# Neural_Interface.net
KiCad netlist of a schematic drawn in Altium Designer
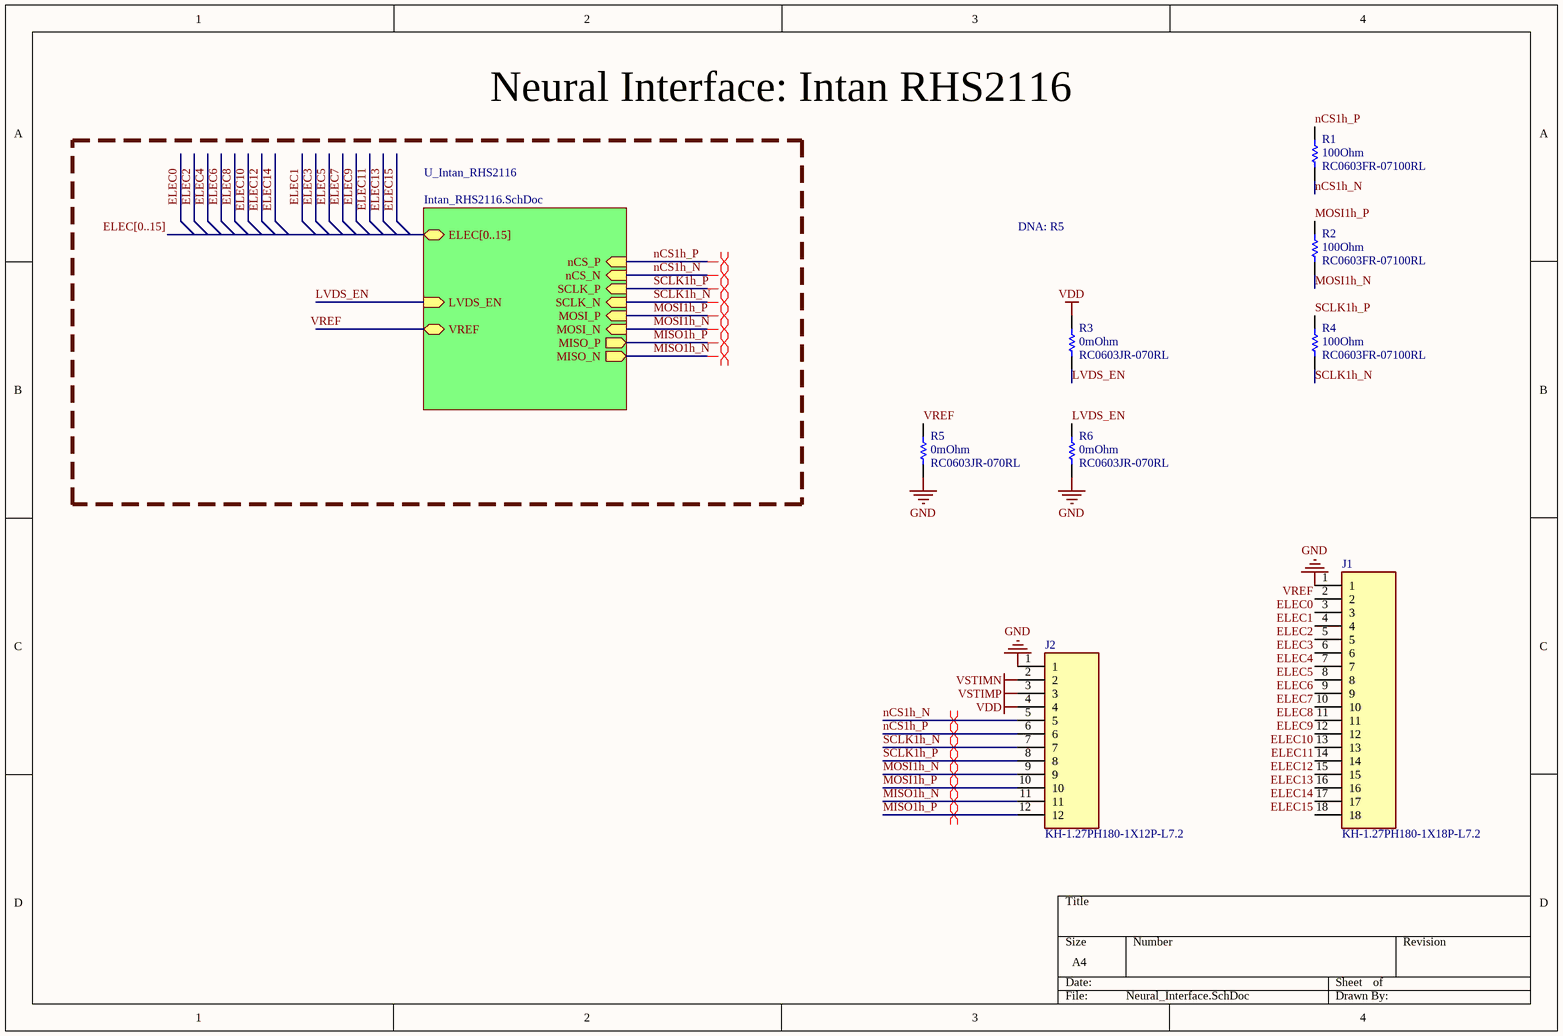
[diagram p0: Neural_Interface.SchDoc]

(export (version "E")
  (design (tool "Eeschema 10.0.6"))
  (components
    (comp (ref "J1")
      (value "KH-1.27PH180-1X18P-L7.2")
      (footprint "KH-1.27PH180-1X18P-L7.2")
      (libsource (lib "Neural_Interface") (part "KH-1.27PH180-1X18P-L7.2"))
    )
    (comp (ref "J2")
      (value "KH-1.27PH180-1X12P-L7.2")
      (footprint "KH-1.27PH180-1X12P-L7.2")
      (libsource (lib "Neural_Interface") (part "KH-1.27PH180-1X12P-L7.2"))
    )
    (comp (ref "R1")
      (value "RC0603FR-07100RL")
      (footprint "RESC1608X55X25ML10T15")
      (description "Chip Resistor, 100 Ohm, +/- 1%, 0.1 W, -55 to 155 degC, 0603 (1608 Metric), RoHS, Tape and Reel")
      (fields
        (field (name "TOLERANCE") "1%")
        (field (name "RESISTANCE") "100Ohm")
        (field (name "MANUFACTURER") "Yageo")
      )
      (libsource (lib "Altium Content Vault") (part "RES-2"))
    )
    (comp (ref "R2")
      (value "RC0603FR-07100RL")
      (footprint "RESC1608X55X25ML10T15")
      (description "Chip Resistor, 100 Ohm, +/- 1%, 0.1 W, -55 to 155 degC, 0603 (1608 Metric), RoHS, Tape and Reel")
      (fields
        (field (name "TOLERANCE") "1%")
        (field (name "RESISTANCE") "100Ohm")
        (field (name "MANUFACTURER") "Yageo")
      )
      (libsource (lib "Altium Content Vault") (part "RES-2"))
    )
    (comp (ref "R3")
      (value "RC0603JR-070RL")
      (footprint "RESC1608X55X25ML10T15")
      (description "Chip Resistor, 0 Ohm, +/- 5%, 0.1 W, -55 to 155 degC, 0603 (1608 Metric), RoHS, Tape and Reel")
      (fields
        (field (name "TOLERANCE") "5%")
        (field (name "RESISTANCE") "0mOhm")
        (field (name "MANUFACTURER") "Yageo")
      )
      (libsource (lib "Altium Content Vault") (part "RES-2"))
    )
    (comp (ref "R4")
      (value "RC0603FR-07100RL")
      (footprint "RESC1608X55X25ML10T15")
      (description "Chip Resistor, 100 Ohm, +/- 1%, 0.1 W, -55 to 155 degC, 0603 (1608 Metric), RoHS, Tape and Reel")
      (fields
        (field (name "TOLERANCE") "1%")
        (field (name "RESISTANCE") "100Ohm")
        (field (name "MANUFACTURER") "Yageo")
      )
      (libsource (lib "Altium Content Vault") (part "RES-2"))
    )
    (comp (ref "R5")
      (value "RC0603JR-070RL")
      (footprint "RESC1608X55X25ML10T15")
      (description "Chip Resistor, 0 Ohm, +/- 5%, 0.1 W, -55 to 155 degC, 0603 (1608 Metric), RoHS, Tape and Reel")
      (fields
        (field (name "TOLERANCE") "5%")
        (field (name "RESISTANCE") "0mOhm")
        (field (name "MANUFACTURER") "Yageo")
      )
      (libsource (lib "Altium Content Vault") (part "RES-2"))
    )
    (comp (ref "R6")
      (value "RC0603JR-070RL")
      (footprint "RESC1608X55X25ML10T15")
      (description "Chip Resistor, 0 Ohm, +/- 5%, 0.1 W, -55 to 155 degC, 0603 (1608 Metric), RoHS, Tape and Reel")
      (fields
        (field (name "TOLERANCE") "5%")
        (field (name "RESISTANCE") "0mOhm")
        (field (name "MANUFACTURER") "Yageo")
      )
      (libsource (lib "Altium Content Vault") (part "RES-2"))
    )
  )
  (nets
    (net (code "1") (name "/ELEC0") (class "Default")
      (node (ref "J1") (pin "3") (pinfunction "3_3") (pintype "passive"))
    )
    (net (code "2") (name "/ELEC1") (class "Default")
      (node (ref "J1") (pin "4") (pinfunction "4_4") (pintype "passive"))
    )
    (net (code "3") (name "/ELEC2") (class "Default")
      (node (ref "J1") (pin "5") (pinfunction "5_5") (pintype "passive"))
    )
    (net (code "4") (name "/ELEC3") (class "Default")
      (node (ref "J1") (pin "6") (pinfunction "6_6") (pintype "passive"))
    )
    (net (code "5") (name "/ELEC4") (class "Default")
      (node (ref "J1") (pin "7") (pinfunction "7_7") (pintype "passive"))
    )
    (net (code "6") (name "/ELEC5") (class "Default")
      (node (ref "J1") (pin "8") (pinfunction "8_8") (pintype "passive"))
    )
    (net (code "7") (name "/ELEC6") (class "Default")
      (node (ref "J1") (pin "9") (pinfunction "9_9") (pintype "passive"))
    )
    (net (code "8") (name "/ELEC7") (class "Default")
      (node (ref "J1") (pin "10") (pinfunction "10_10") (pintype "passive"))
    )
    (net (code "9") (name "/ELEC8") (class "Default")
      (node (ref "J1") (pin "11") (pinfunction "11_11") (pintype "passive"))
    )
    (net (code "10") (name "/ELEC9") (class "Default")
      (node (ref "J1") (pin "12") (pinfunction "12_12") (pintype "passive"))
    )
    (net (code "11") (name "/ELEC10") (class "Default")
      (node (ref "J1") (pin "13") (pinfunction "13_13") (pintype "passive"))
    )
    (net (code "12") (name "/ELEC11") (class "Default")
      (node (ref "J1") (pin "14") (pinfunction "14_14") (pintype "passive"))
    )
    (net (code "13") (name "/ELEC12") (class "Default")
      (node (ref "J1") (pin "15") (pinfunction "15_15") (pintype "passive"))
    )
    (net (code "14") (name "/ELEC13") (class "Default")
      (node (ref "J1") (pin "16") (pinfunction "16_16") (pintype "passive"))
    )
    (net (code "15") (name "/ELEC14") (class "Default")
      (node (ref "J1") (pin "17") (pinfunction "17_17") (pintype "passive"))
    )
    (net (code "16") (name "/ELEC15") (class "Default")
      (node (ref "J1") (pin "18") (pinfunction "18_18") (pintype "passive"))
    )
    (net (code "18") (name "/LVDS_EN") (class "Default")
      (node (ref "R3") (pin "1") (pinfunction "1_1") (pintype "passive"))
      (node (ref "R6") (pin "2") (pinfunction "2_2") (pintype "passive"))
    )
    (net (code "19") (name "/MISO1h_N") (class "Default")
      (node (ref "J2") (pin "11") (pinfunction "11_11") (pintype "passive"))
    )
    (net (code "20") (name "/MISO1h_P") (class "Default")
      (node (ref "J2") (pin "12") (pinfunction "12_12") (pintype "passive"))
    )
    (net (code "21") (name "/MOSI1h_N") (class "Default")
      (node (ref "J2") (pin "9") (pinfunction "9_9") (pintype "passive"))
      (node (ref "R2") (pin "1") (pinfunction "1_1") (pintype "passive"))
    )
    (net (code "22") (name "/MOSI1h_P") (class "Default")
      (node (ref "J2") (pin "10") (pinfunction "10_10") (pintype "passive"))
      (node (ref "R2") (pin "2") (pinfunction "2_2") (pintype "passive"))
    )
    (net (code "23") (name "/SCLK1h_N") (class "Default")
      (node (ref "J2") (pin "7") (pinfunction "7_7") (pintype "passive"))
      (node (ref "R4") (pin "1") (pinfunction "1_1") (pintype "passive"))
    )
    (net (code "24") (name "/SCLK1h_P") (class "Default")
      (node (ref "J2") (pin "8") (pinfunction "8_8") (pintype "passive"))
      (node (ref "R4") (pin "2") (pinfunction "2_2") (pintype "passive"))
    )
    (net (code "25") (name "/VREF") (class "Default")
      (node (ref "J1") (pin "2") (pinfunction "2_2") (pintype "passive"))
      (node (ref "R5") (pin "2") (pinfunction "2_2") (pintype "passive"))
    )
    (net (code "26") (name "/nCS1h_N") (class "Default")
      (node (ref "J2") (pin "5") (pinfunction "5_5") (pintype "passive"))
      (node (ref "R1") (pin "1") (pinfunction "1_1") (pintype "passive"))
    )
    (net (code "27") (name "/nCS1h_P") (class "Default")
      (node (ref "J2") (pin "6") (pinfunction "6_6") (pintype "passive"))
      (node (ref "R1") (pin "2") (pinfunction "2_2") (pintype "passive"))
    )
    (net (code "28") (name "GND") (class "Default")
      (node (ref "J1") (pin "1") (pinfunction "1_1") (pintype "passive"))
      (node (ref "J2") (pin "1") (pinfunction "1_1") (pintype "passive"))
      (node (ref "R5") (pin "1") (pinfunction "1_1") (pintype "passive"))
      (node (ref "R6") (pin "1") (pinfunction "1_1") (pintype "passive"))
    )
    (net (code "29") (name "VDD") (class "Default")
      (node (ref "J2") (pin "4") (pinfunction "4_4") (pintype "passive"))
      (node (ref "R3") (pin "2") (pinfunction "2_2") (pintype "passive"))
    )
    (net (code "30") (name "VSTIMN") (class "Default")
      (node (ref "J2") (pin "2") (pinfunction "2_2") (pintype "passive"))
    )
    (net (code "31") (name "VSTIMP") (class "Default")
      (node (ref "J2") (pin "3") (pinfunction "3_3") (pintype "passive"))
    )
  )
)
